# DM1097_RJ45.net
KiCad netlist of a schematic drawn in Altium Designer
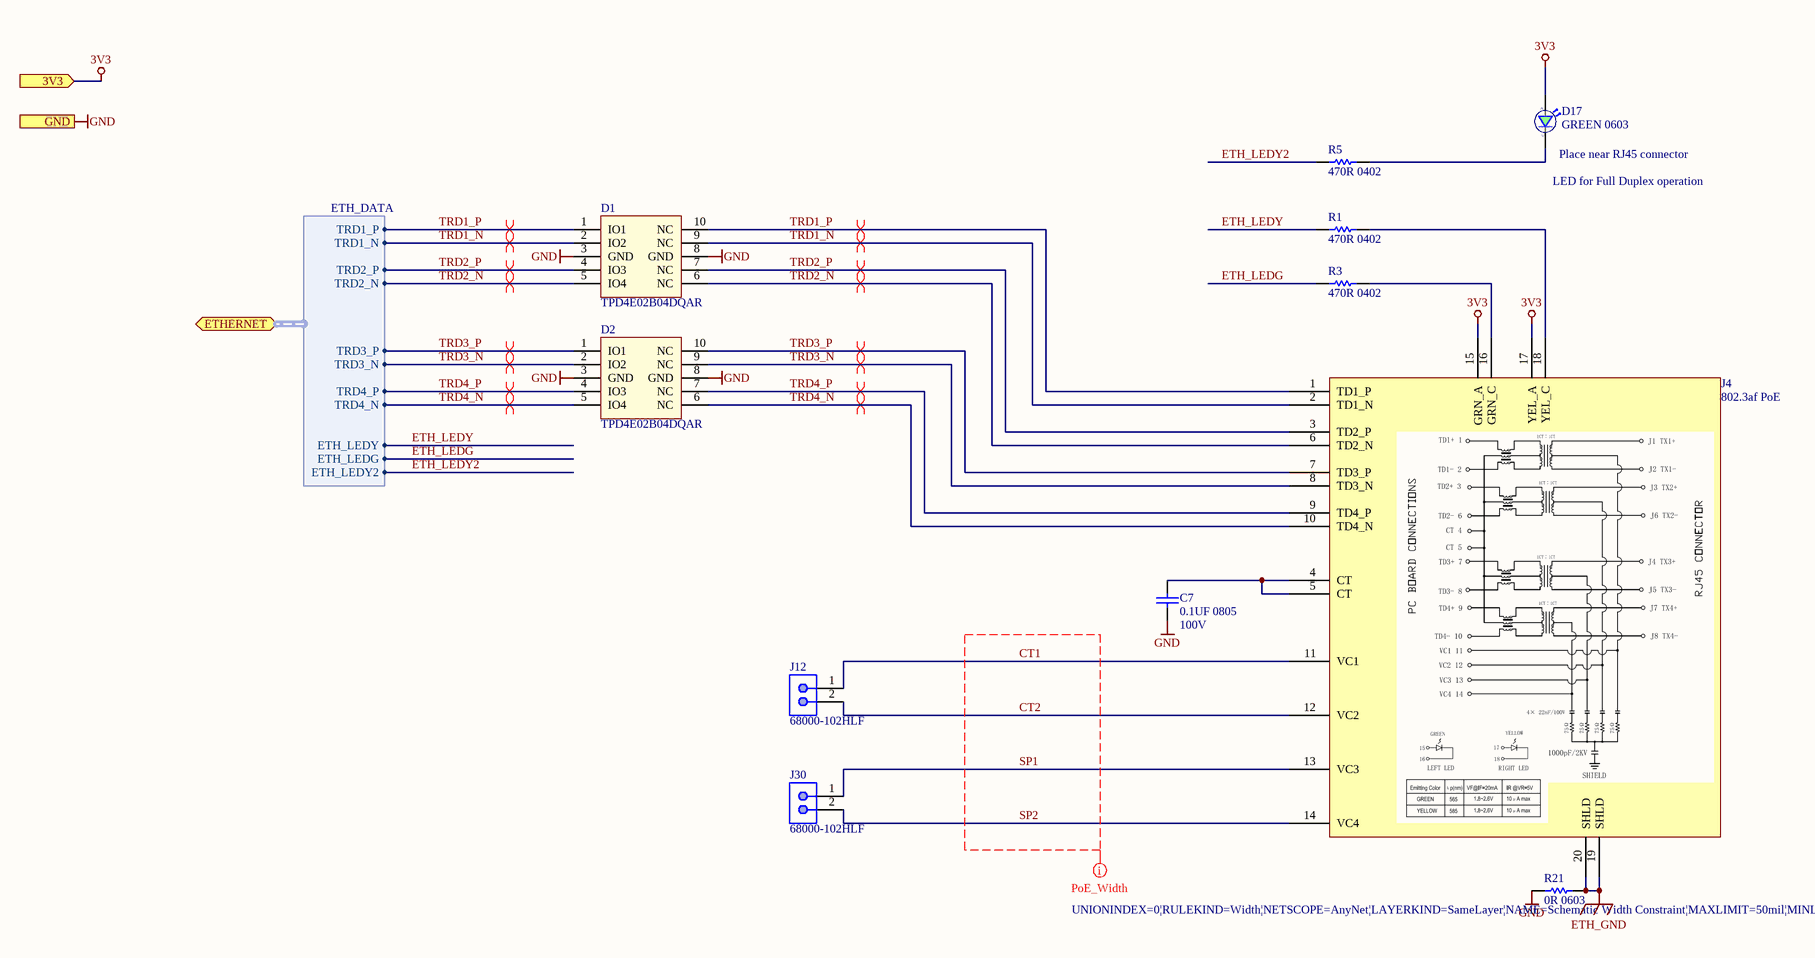
[diagram p0: DM1097_RJ45.SchDoc]

(export (version "E")
  (design (tool "Eeschema 10.0.6"))
  (components
    (comp (ref "C7")
      (value "0.1UF 0805")
      (footprint "CAPC0805(2012)145_N")
      (description "CAP CER 0.1UF 100V X7R 0805")
      (fields (field (name "TOLERANCE") "10%") (field (name "VOLTAGE RATING") "100V"))
      (libsource (lib "DM1097_SchLib") (part "CL21B104KCFNNNE"))
    )
    (comp (ref "D1")
      (value "TPD4E02B04DQAR")
      (footprint "LuxonisMaster:TPD4E02B04DQAR")
      (libsource (lib "LuxonisMaster") (part "TPD4E02B04DQAR"))
    )
    (comp (ref "D2")
      (value "TPD4E02B04DQAR")
      (footprint "LuxonisMaster:TPD4E02B04DQAR")
      (libsource (lib "LuxonisMaster") (part "TPD4E02B04DQAR"))
    )
    (comp (ref "D17")
      (value "GREEN 0603")
      (footprint "LuxonisMaster:SML_D1xx8W")
      (description "LED GREEN DIFFUSED 0603 SMD Green 572nm LED Indication - Discrete 2.2V 0603 (1608 Metric)")
      (fields (field (name "MANUFACTURER") "Rohm") (field (name "MANUFACTURER PART NUMBER") "SML-D12M8WT86"))
      (libsource (lib "LuxonisMaster") (part "SML-D12M8WT86"))
    )
    (comp (ref "J4")
      (value "802.3af PoE")
      (footprint "DM1097_PcbLib:TRJG0926HENL")
      (description "CONN MAGJACK 1PORT 1000 BASET")
      (libsource (lib "DM1097_SchLib") (part "TRJG0926HENL"))
    )
    (comp (ref "J12")
      (value "68000-102HLF")
      (footprint "LuxonisMaster:68000-102HLF")
      (description "CONN HEADER VERT 2POS 2.54MM")
      (libsource (lib "LuxonisMaster") (part "68000-102HLF"))
    )
    (comp (ref "J30")
      (value "68000-102HLF")
      (footprint "LuxonisMaster:68000-102HLF")
      (description "CONN HEADER VERT 2POS 2.54MM")
      (libsource (lib "LuxonisMaster") (part "68000-102HLF"))
    )
    (comp (ref "R1")
      (value "470R 0402")
      (footprint "RES_Altium_Vault_Generic:RESC0402(1005)_N")
      (description "RES SMD 470 OHM 1% 1/16W 0402")
      (fields (field (name "TOLERANCE") "1%"))
      (libsource (lib "LuxonisMaster") (part "CRCW0402470RFKED"))
    )
    (comp (ref "R3")
      (value "470R 0402")
      (footprint "RES_Altium_Vault_Generic:RESC0402(1005)_N")
      (description "RES SMD 470 OHM 1% 1/16W 0402")
      (fields (field (name "TOLERANCE") "1%"))
      (libsource (lib "LuxonisMaster") (part "CRCW0402470RFKED"))
    )
    (comp (ref "R5")
      (value "470R 0402")
      (footprint "RES_Altium_Vault_Generic:RESC0402(1005)_N")
      (description "RES SMD 470 OHM 1% 1/16W 0402")
      (fields (field (name "TOLERANCE") "1%"))
      (libsource (lib "LuxonisMaster") (part "CRCW0402470RFKED"))
    )
    (comp (ref "R21")
      (value "0R 0603")
      (footprint "RES_Altium_Vault_Generic:RESC0603(1608)_N")
      (fields (field (name "TOLERANCE") "5%"))
      (libsource (lib "LuxonisMaster") (part "CRCW06030000Z0EA"))
    )
  )
  (nets
    (net (code "2") (name "/CT1") (class "Default")
      (node (ref "J12") (pin "1") (pinfunction "1_1") (pintype "passive"))
      (node (ref "J4") (pin "11") (pinfunction "VC1_11") (pintype "passive"))
    )
    (net (code "3") (name "/CT2") (class "Default")
      (node (ref "J12") (pin "2") (pinfunction "2_2") (pintype "passive"))
      (node (ref "J4") (pin "12") (pinfunction "VC2_12") (pintype "passive"))
    )
    (net (code "4") (name "/ETH_LEDG") (class "Default")
      (node (ref "R3") (pin "1") (pinfunction "1_1") (pintype "passive"))
    )
    (net (code "5") (name "/ETH_LEDY") (class "Default")
      (node (ref "R1") (pin "1") (pinfunction "1_1") (pintype "passive"))
    )
    (net (code "6") (name "/ETH_LEDY2") (class "Default")
      (node (ref "R5") (pin "1") (pinfunction "1_1") (pintype "passive"))
    )
    (net (code "7") (name "/SP1") (class "Default")
      (node (ref "J30") (pin "1") (pinfunction "1_1") (pintype "passive"))
      (node (ref "J4") (pin "13") (pinfunction "VC3_13") (pintype "passive"))
    )
    (net (code "8") (name "/SP2") (class "Default")
      (node (ref "J30") (pin "2") (pinfunction "2_2") (pintype "passive"))
      (node (ref "J4") (pin "14") (pinfunction "VC4_14") (pintype "passive"))
    )
    (net (code "9") (name "/TRD1_N") (class "Default")
      (node (ref "D1") (pin "2") (pinfunction "IO2_2") (pintype "passive"))
      (node (ref "D1") (pin "9") (pinfunction "NC_9") (pintype "passive"))
      (node (ref "J4") (pin "2") (pinfunction "TD1_N_2") (pintype "passive"))
    )
    (net (code "10") (name "/TRD1_P") (class "Default")
      (node (ref "D1") (pin "1") (pinfunction "IO1_1") (pintype "passive"))
      (node (ref "D1") (pin "10") (pinfunction "NC_10") (pintype "passive"))
      (node (ref "J4") (pin "1") (pinfunction "TD1_P_1") (pintype "passive"))
    )
    (net (code "11") (name "/TRD2_N") (class "Default")
      (node (ref "D1") (pin "5") (pinfunction "IO4_5") (pintype "passive"))
      (node (ref "D1") (pin "6") (pinfunction "NC_6") (pintype "passive"))
      (node (ref "J4") (pin "6") (pinfunction "TD2_N_6") (pintype "passive"))
    )
    (net (code "12") (name "/TRD2_P") (class "Default")
      (node (ref "D1") (pin "4") (pinfunction "IO3_4") (pintype "passive"))
      (node (ref "D1") (pin "7") (pinfunction "NC_7") (pintype "passive"))
      (node (ref "J4") (pin "3") (pinfunction "TD2_P_3") (pintype "passive"))
    )
    (net (code "13") (name "/TRD3_N") (class "Default")
      (node (ref "D2") (pin "2") (pinfunction "IO2_2") (pintype "passive"))
      (node (ref "D2") (pin "9") (pinfunction "NC_9") (pintype "passive"))
      (node (ref "J4") (pin "8") (pinfunction "TD3_N_8") (pintype "passive"))
    )
    (net (code "14") (name "/TRD3_P") (class "Default")
      (node (ref "D2") (pin "1") (pinfunction "IO1_1") (pintype "passive"))
      (node (ref "D2") (pin "10") (pinfunction "NC_10") (pintype "passive"))
      (node (ref "J4") (pin "7") (pinfunction "TD3_P_7") (pintype "passive"))
    )
    (net (code "15") (name "/TRD4_N") (class "Default")
      (node (ref "D2") (pin "5") (pinfunction "IO4_5") (pintype "passive"))
      (node (ref "D2") (pin "6") (pinfunction "NC_6") (pintype "passive"))
      (node (ref "J4") (pin "10") (pinfunction "TD4_N_10") (pintype "passive"))
    )
    (net (code "16") (name "/TRD4_P") (class "Default")
      (node (ref "D2") (pin "4") (pinfunction "IO3_4") (pintype "passive"))
      (node (ref "D2") (pin "7") (pinfunction "NC_7") (pintype "passive"))
      (node (ref "J4") (pin "9") (pinfunction "TD4_P_9") (pintype "passive"))
    )
    (net (code "18") (name "3V3") (class "Default")
      (node (ref "D17") (pin "2") (pinfunction "A_2") (pintype "passive"))
      (node (ref "J4") (pin "15") (pinfunction "GRN_A_15") (pintype "passive"))
      (node (ref "J4") (pin "17") (pinfunction "YEL_A_17") (pintype "passive"))
    )
    (net (code "19") (name "ETH_GND") (class "Default")
      (node (ref "J4") (pin "19") (pinfunction "SHLD_19") (pintype "passive"))
      (node (ref "J4") (pin "20") (pinfunction "SHLD_20") (pintype "passive"))
      (node (ref "R21") (pin "2") (pinfunction "2_2") (pintype "passive"))
    )
    (net (code "20") (name "GND") (class "Default")
      (node (ref "C7") (pin "1") (pinfunction "1_1") (pintype "passive"))
      (node (ref "D1") (pin "3") (pinfunction "GND_3") (pintype "passive"))
      (node (ref "D1") (pin "8") (pinfunction "GND_8") (pintype "passive"))
      (node (ref "D2") (pin "3") (pinfunction "GND_3") (pintype "passive"))
      (node (ref "D2") (pin "8") (pinfunction "GND_8") (pintype "passive"))
      (node (ref "R21") (pin "1") (pinfunction "1_1") (pintype "passive"))
    )
    (net (code "21") (name "Net-(C7-Pad2)") (class "Default")
      (node (ref "C7") (pin "2") (pinfunction "2_2") (pintype "passive"))
      (node (ref "J4") (pin "4") (pinfunction "CT_4") (pintype "passive"))
      (node (ref "J4") (pin "5") (pinfunction "CT_5") (pintype "passive"))
    )
    (net (code "22") (name "Net-(D17-C)") (class "Default")
      (node (ref "D17") (pin "1") (pinfunction "C_1") (pintype "passive"))
      (node (ref "R5") (pin "2") (pinfunction "2_2") (pintype "passive"))
    )
    (net (code "23") (name "Net-(J4-GRN_C)") (class "Default")
      (node (ref "J4") (pin "16") (pinfunction "GRN_C_16") (pintype "passive"))
      (node (ref "R3") (pin "2") (pinfunction "2_2") (pintype "passive"))
    )
    (net (code "24") (name "Net-(J4-YEL_C)") (class "Default")
      (node (ref "J4") (pin "18") (pinfunction "YEL_C_18") (pintype "passive"))
      (node (ref "R1") (pin "2") (pinfunction "2_2") (pintype "passive"))
    )
  )
)
